# ECE_362_mini_project.net
KiCad netlist of a schematic drawn in EAGLE
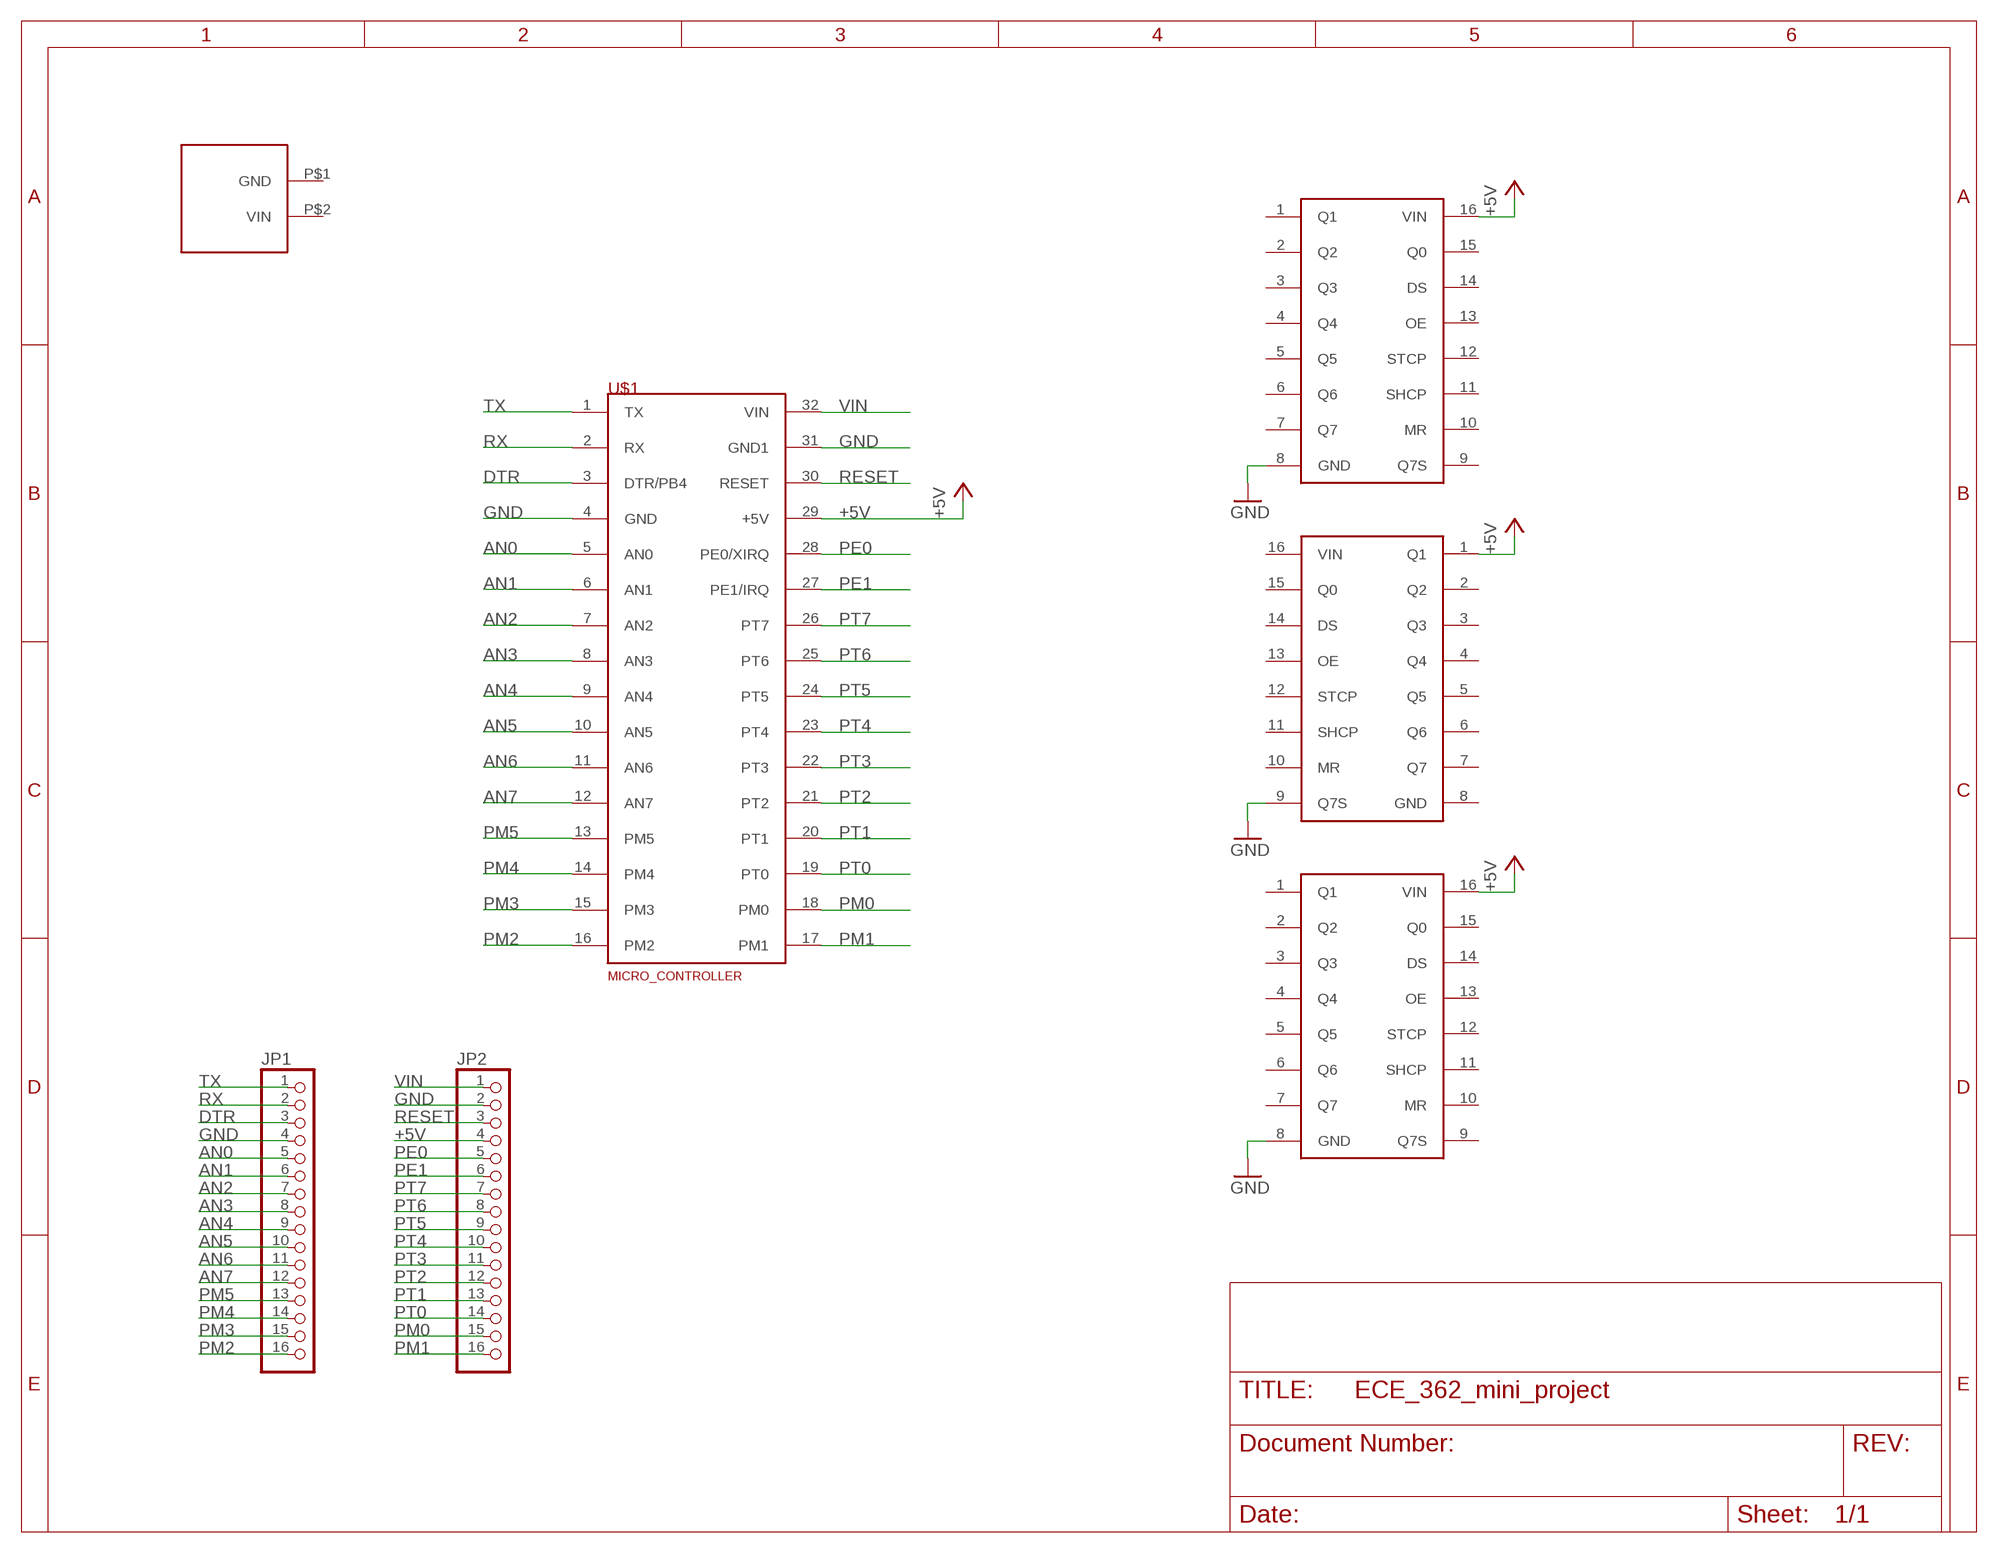
[diagram p0: schematic, sheet 1]

(export (version "E")
  (design (tool "Eeschema 10.0.6"))
  (components
    (comp (ref "JP1")
      (value "PINHD-1X16")
      (footprint "eagle-import:1X16")
      (libsource (lib "eagle-import") (part "PINHD-1X16"))
    )
    (comp (ref "JP2")
      (value "PINHD-1X16")
      (footprint "eagle-import:1X16")
      (libsource (lib "eagle-import") (part "PINHD-1X16"))
    )
    (comp (ref "U$1")
      (value "MICRO_CONTROLLER")
      (footprint "eagle-import:MICRO_CONTROLLER")
      (libsource (lib "eagle-import") (part "MICRO_CONTROLLER"))
    )
    (comp (ref "U$2")
      (value "SHIFT_REGISTER")
      (footprint "eagle-import:N5")
      (libsource (lib "eagle-import") (part "SHIFT_REGISTER"))
    )
    (comp (ref "U$3")
      (value "XT60")
      (footprint "eagle-import:XT60")
      (libsource (lib "eagle-import") (part "XT60"))
    )
    (comp (ref "U$4")
      (value "SHIFT_REGISTER")
      (footprint "eagle-import:N5")
      (libsource (lib "eagle-import") (part "SHIFT_REGISTER"))
    )
    (comp (ref "U$5")
      (value "SHIFT_REGISTER")
      (footprint "eagle-import:N5")
      (libsource (lib "eagle-import") (part "SHIFT_REGISTER"))
    )
  )
  (nets
    (net (code "1") (name "+5V") (class "Default")
      (node (ref "JP2") (pin "4") (pinfunction "4_4") (pintype "passive"))
      (node (ref "U$1") (pin "29") (pinfunction "+5V_29") (pintype "bidirectional"))
      (node (ref "U$2") (pin "16") (pinfunction "VIN_16") (pintype "bidirectional"))
      (node (ref "U$4") (pin "1") (pinfunction "Q1_1") (pintype "bidirectional"))
      (node (ref "U$5") (pin "16") (pinfunction "VIN_16") (pintype "bidirectional"))
    )
    (net (code "2") (name "/AN0") (class "Default")
      (node (ref "JP1") (pin "5") (pinfunction "5_5") (pintype "passive"))
      (node (ref "U$1") (pin "5") (pinfunction "AN0_5") (pintype "bidirectional"))
    )
    (net (code "3") (name "/AN1") (class "Default")
      (node (ref "JP1") (pin "6") (pinfunction "6_6") (pintype "passive"))
      (node (ref "U$1") (pin "6") (pinfunction "AN1_6") (pintype "bidirectional"))
    )
    (net (code "4") (name "/AN2") (class "Default")
      (node (ref "JP1") (pin "7") (pinfunction "7_7") (pintype "passive"))
      (node (ref "U$1") (pin "7") (pinfunction "AN2_7") (pintype "bidirectional"))
    )
    (net (code "5") (name "/AN3") (class "Default")
      (node (ref "JP1") (pin "8") (pinfunction "8_8") (pintype "passive"))
      (node (ref "U$1") (pin "8") (pinfunction "AN3_8") (pintype "bidirectional"))
    )
    (net (code "6") (name "/AN4") (class "Default")
      (node (ref "JP1") (pin "9") (pinfunction "9_9") (pintype "passive"))
      (node (ref "U$1") (pin "9") (pinfunction "AN4_9") (pintype "bidirectional"))
    )
    (net (code "7") (name "/AN5") (class "Default")
      (node (ref "JP1") (pin "10") (pinfunction "10_10") (pintype "passive"))
      (node (ref "U$1") (pin "10") (pinfunction "AN5_10") (pintype "bidirectional"))
    )
    (net (code "8") (name "/AN6") (class "Default")
      (node (ref "JP1") (pin "11") (pinfunction "11_11") (pintype "passive"))
      (node (ref "U$1") (pin "11") (pinfunction "AN6_11") (pintype "bidirectional"))
    )
    (net (code "9") (name "/AN7") (class "Default")
      (node (ref "JP1") (pin "12") (pinfunction "12_12") (pintype "passive"))
      (node (ref "U$1") (pin "12") (pinfunction "AN7_12") (pintype "bidirectional"))
    )
    (net (code "10") (name "/DTR") (class "Default")
      (node (ref "JP1") (pin "3") (pinfunction "3_3") (pintype "passive"))
      (node (ref "U$1") (pin "3") (pinfunction "DTR/PB4_3") (pintype "bidirectional"))
    )
    (net (code "11") (name "/PE0") (class "Default")
      (node (ref "JP2") (pin "5") (pinfunction "5_5") (pintype "passive"))
      (node (ref "U$1") (pin "28") (pinfunction "PE0/XIRQ_28") (pintype "bidirectional"))
    )
    (net (code "12") (name "/PE1") (class "Default")
      (node (ref "JP2") (pin "6") (pinfunction "6_6") (pintype "passive"))
      (node (ref "U$1") (pin "27") (pinfunction "PE1/IRQ_27") (pintype "bidirectional"))
    )
    (net (code "13") (name "/PM0") (class "Default")
      (node (ref "JP2") (pin "15") (pinfunction "15_15") (pintype "passive"))
      (node (ref "U$1") (pin "18") (pinfunction "PM0_18") (pintype "bidirectional"))
    )
    (net (code "14") (name "/PM1") (class "Default")
      (node (ref "JP2") (pin "16") (pinfunction "16_16") (pintype "passive"))
      (node (ref "U$1") (pin "17") (pinfunction "PM1_17") (pintype "bidirectional"))
    )
    (net (code "15") (name "/PM2") (class "Default")
      (node (ref "JP1") (pin "16") (pinfunction "16_16") (pintype "passive"))
      (node (ref "U$1") (pin "16") (pinfunction "PM2_16") (pintype "bidirectional"))
    )
    (net (code "16") (name "/PM3") (class "Default")
      (node (ref "JP1") (pin "15") (pinfunction "15_15") (pintype "passive"))
      (node (ref "U$1") (pin "15") (pinfunction "PM3_15") (pintype "bidirectional"))
    )
    (net (code "17") (name "/PM4") (class "Default")
      (node (ref "JP1") (pin "14") (pinfunction "14_14") (pintype "passive"))
      (node (ref "U$1") (pin "14") (pinfunction "PM4_14") (pintype "bidirectional"))
    )
    (net (code "18") (name "/PM5") (class "Default")
      (node (ref "JP1") (pin "13") (pinfunction "13_13") (pintype "passive"))
      (node (ref "U$1") (pin "13") (pinfunction "PM5_13") (pintype "bidirectional"))
    )
    (net (code "19") (name "/PT0") (class "Default")
      (node (ref "JP2") (pin "14") (pinfunction "14_14") (pintype "passive"))
      (node (ref "U$1") (pin "19") (pinfunction "PT0_19") (pintype "bidirectional"))
    )
    (net (code "20") (name "/PT1") (class "Default")
      (node (ref "JP2") (pin "13") (pinfunction "13_13") (pintype "passive"))
      (node (ref "U$1") (pin "20") (pinfunction "PT1_20") (pintype "bidirectional"))
    )
    (net (code "21") (name "/PT2") (class "Default")
      (node (ref "JP2") (pin "12") (pinfunction "12_12") (pintype "passive"))
      (node (ref "U$1") (pin "21") (pinfunction "PT2_21") (pintype "bidirectional"))
    )
    (net (code "22") (name "/PT3") (class "Default")
      (node (ref "JP2") (pin "11") (pinfunction "11_11") (pintype "passive"))
      (node (ref "U$1") (pin "22") (pinfunction "PT3_22") (pintype "bidirectional"))
    )
    (net (code "23") (name "/PT4") (class "Default")
      (node (ref "JP2") (pin "10") (pinfunction "10_10") (pintype "passive"))
      (node (ref "U$1") (pin "23") (pinfunction "PT4_23") (pintype "bidirectional"))
    )
    (net (code "24") (name "/PT5") (class "Default")
      (node (ref "JP2") (pin "9") (pinfunction "9_9") (pintype "passive"))
      (node (ref "U$1") (pin "24") (pinfunction "PT5_24") (pintype "bidirectional"))
    )
    (net (code "25") (name "/PT6") (class "Default")
      (node (ref "JP2") (pin "8") (pinfunction "8_8") (pintype "passive"))
      (node (ref "U$1") (pin "25") (pinfunction "PT6_25") (pintype "bidirectional"))
    )
    (net (code "26") (name "/PT7") (class "Default")
      (node (ref "JP2") (pin "7") (pinfunction "7_7") (pintype "passive"))
      (node (ref "U$1") (pin "26") (pinfunction "PT7_26") (pintype "bidirectional"))
    )
    (net (code "27") (name "/RESET") (class "Default")
      (node (ref "JP2") (pin "3") (pinfunction "3_3") (pintype "passive"))
      (node (ref "U$1") (pin "30") (pinfunction "RESET_30") (pintype "bidirectional"))
    )
    (net (code "28") (name "/RX") (class "Default")
      (node (ref "JP1") (pin "2") (pinfunction "2_2") (pintype "passive"))
      (node (ref "U$1") (pin "2") (pinfunction "RX_2") (pintype "bidirectional"))
    )
    (net (code "29") (name "/TX") (class "Default")
      (node (ref "JP1") (pin "1") (pinfunction "1_1") (pintype "passive"))
      (node (ref "U$1") (pin "1") (pinfunction "TX_1") (pintype "bidirectional"))
    )
    (net (code "30") (name "/VIN") (class "Default")
      (node (ref "JP2") (pin "1") (pinfunction "1_1") (pintype "passive"))
      (node (ref "U$1") (pin "32") (pinfunction "VIN_32") (pintype "bidirectional"))
    )
    (net (code "31") (name "GND") (class "Default")
      (node (ref "JP1") (pin "4") (pinfunction "4_4") (pintype "passive"))
      (node (ref "JP2") (pin "2") (pinfunction "2_2") (pintype "passive"))
      (node (ref "U$1") (pin "31") (pinfunction "GND1_31") (pintype "bidirectional"))
      (node (ref "U$1") (pin "4") (pinfunction "GND_4") (pintype "bidirectional"))
      (node (ref "U$2") (pin "8") (pinfunction "GND_8") (pintype "bidirectional"))
      (node (ref "U$4") (pin "9") (pinfunction "Q7S_9") (pintype "bidirectional"))
      (node (ref "U$5") (pin "8") (pinfunction "GND_8") (pintype "bidirectional"))
    )
    (net (code "32") (name "unconnected-(U$2-DS-Pad14)") (class "Default")
      (node (ref "U$2") (pin "14") (pinfunction "DS_14") (pintype "bidirectional"))
    )
    (net (code "33") (name "unconnected-(U$2-MR-Pad10)") (class "Default")
      (node (ref "U$2") (pin "10") (pinfunction "MR_10") (pintype "bidirectional"))
    )
    (net (code "34") (name "unconnected-(U$2-OE-Pad13)") (class "Default")
      (node (ref "U$2") (pin "13") (pinfunction "OE_13") (pintype "bidirectional"))
    )
    (net (code "35") (name "unconnected-(U$2-Q0-Pad15)") (class "Default")
      (node (ref "U$2") (pin "15") (pinfunction "Q0_15") (pintype "bidirectional"))
    )
    (net (code "36") (name "unconnected-(U$2-Q1-Pad1)") (class "Default")
      (node (ref "U$2") (pin "1") (pinfunction "Q1_1") (pintype "bidirectional"))
    )
    (net (code "37") (name "unconnected-(U$2-Q2-Pad2)") (class "Default")
      (node (ref "U$2") (pin "2") (pinfunction "Q2_2") (pintype "bidirectional"))
    )
    (net (code "38") (name "unconnected-(U$2-Q3-Pad3)") (class "Default")
      (node (ref "U$2") (pin "3") (pinfunction "Q3_3") (pintype "bidirectional"))
    )
    (net (code "39") (name "unconnected-(U$2-Q4-Pad4)") (class "Default")
      (node (ref "U$2") (pin "4") (pinfunction "Q4_4") (pintype "bidirectional"))
    )
    (net (code "40") (name "unconnected-(U$2-Q5-Pad5)") (class "Default")
      (node (ref "U$2") (pin "5") (pinfunction "Q5_5") (pintype "bidirectional"))
    )
    (net (code "41") (name "unconnected-(U$2-Q6-Pad6)") (class "Default")
      (node (ref "U$2") (pin "6") (pinfunction "Q6_6") (pintype "bidirectional"))
    )
    (net (code "42") (name "unconnected-(U$2-Q7-Pad7)") (class "Default")
      (node (ref "U$2") (pin "7") (pinfunction "Q7_7") (pintype "bidirectional"))
    )
    (net (code "43") (name "unconnected-(U$2-Q7S-Pad9)") (class "Default")
      (node (ref "U$2") (pin "9") (pinfunction "Q7S_9") (pintype "bidirectional"))
    )
    (net (code "44") (name "unconnected-(U$2-SHCP-Pad11)") (class "Default")
      (node (ref "U$2") (pin "11") (pinfunction "SHCP_11") (pintype "bidirectional"))
    )
    (net (code "45") (name "unconnected-(U$2-STCP-Pad12)") (class "Default")
      (node (ref "U$2") (pin "12") (pinfunction "STCP_12") (pintype "bidirectional"))
    )
    (net (code "46") (name "unconnected-(U$3-GND-PadP$1)") (class "Default")
      (node (ref "U$3") (pin "P$1") (pinfunction "GND_P$1") (pintype "bidirectional"))
    )
    (net (code "47") (name "unconnected-(U$3-VIN-PadP$2)") (class "Default")
      (node (ref "U$3") (pin "P$2") (pinfunction "VIN_P$2") (pintype "bidirectional"))
    )
    (net (code "48") (name "unconnected-(U$4-DS-Pad14)") (class "Default")
      (node (ref "U$4") (pin "14") (pinfunction "DS_14") (pintype "bidirectional"))
    )
    (net (code "49") (name "unconnected-(U$4-GND-Pad8)") (class "Default")
      (node (ref "U$4") (pin "8") (pinfunction "GND_8") (pintype "bidirectional"))
    )
    (net (code "50") (name "unconnected-(U$4-MR-Pad10)") (class "Default")
      (node (ref "U$4") (pin "10") (pinfunction "MR_10") (pintype "bidirectional"))
    )
    (net (code "51") (name "unconnected-(U$4-OE-Pad13)") (class "Default")
      (node (ref "U$4") (pin "13") (pinfunction "OE_13") (pintype "bidirectional"))
    )
    (net (code "52") (name "unconnected-(U$4-Q0-Pad15)") (class "Default")
      (node (ref "U$4") (pin "15") (pinfunction "Q0_15") (pintype "bidirectional"))
    )
    (net (code "53") (name "unconnected-(U$4-Q2-Pad2)") (class "Default")
      (node (ref "U$4") (pin "2") (pinfunction "Q2_2") (pintype "bidirectional"))
    )
    (net (code "54") (name "unconnected-(U$4-Q3-Pad3)") (class "Default")
      (node (ref "U$4") (pin "3") (pinfunction "Q3_3") (pintype "bidirectional"))
    )
    (net (code "55") (name "unconnected-(U$4-Q4-Pad4)") (class "Default")
      (node (ref "U$4") (pin "4") (pinfunction "Q4_4") (pintype "bidirectional"))
    )
    (net (code "56") (name "unconnected-(U$4-Q5-Pad5)") (class "Default")
      (node (ref "U$4") (pin "5") (pinfunction "Q5_5") (pintype "bidirectional"))
    )
    (net (code "57") (name "unconnected-(U$4-Q6-Pad6)") (class "Default")
      (node (ref "U$4") (pin "6") (pinfunction "Q6_6") (pintype "bidirectional"))
    )
    (net (code "58") (name "unconnected-(U$4-Q7-Pad7)") (class "Default")
      (node (ref "U$4") (pin "7") (pinfunction "Q7_7") (pintype "bidirectional"))
    )
    (net (code "59") (name "unconnected-(U$4-SHCP-Pad11)") (class "Default")
      (node (ref "U$4") (pin "11") (pinfunction "SHCP_11") (pintype "bidirectional"))
    )
    (net (code "60") (name "unconnected-(U$4-STCP-Pad12)") (class "Default")
      (node (ref "U$4") (pin "12") (pinfunction "STCP_12") (pintype "bidirectional"))
    )
    (net (code "61") (name "unconnected-(U$4-VIN-Pad16)") (class "Default")
      (node (ref "U$4") (pin "16") (pinfunction "VIN_16") (pintype "bidirectional"))
    )
    (net (code "62") (name "unconnected-(U$5-DS-Pad14)") (class "Default")
      (node (ref "U$5") (pin "14") (pinfunction "DS_14") (pintype "bidirectional"))
    )
    (net (code "63") (name "unconnected-(U$5-MR-Pad10)") (class "Default")
      (node (ref "U$5") (pin "10") (pinfunction "MR_10") (pintype "bidirectional"))
    )
    (net (code "64") (name "unconnected-(U$5-OE-Pad13)") (class "Default")
      (node (ref "U$5") (pin "13") (pinfunction "OE_13") (pintype "bidirectional"))
    )
    (net (code "65") (name "unconnected-(U$5-Q0-Pad15)") (class "Default")
      (node (ref "U$5") (pin "15") (pinfunction "Q0_15") (pintype "bidirectional"))
    )
    (net (code "66") (name "unconnected-(U$5-Q1-Pad1)") (class "Default")
      (node (ref "U$5") (pin "1") (pinfunction "Q1_1") (pintype "bidirectional"))
    )
    (net (code "67") (name "unconnected-(U$5-Q2-Pad2)") (class "Default")
      (node (ref "U$5") (pin "2") (pinfunction "Q2_2") (pintype "bidirectional"))
    )
    (net (code "68") (name "unconnected-(U$5-Q3-Pad3)") (class "Default")
      (node (ref "U$5") (pin "3") (pinfunction "Q3_3") (pintype "bidirectional"))
    )
    (net (code "69") (name "unconnected-(U$5-Q4-Pad4)") (class "Default")
      (node (ref "U$5") (pin "4") (pinfunction "Q4_4") (pintype "bidirectional"))
    )
    (net (code "70") (name "unconnected-(U$5-Q5-Pad5)") (class "Default")
      (node (ref "U$5") (pin "5") (pinfunction "Q5_5") (pintype "bidirectional"))
    )
    (net (code "71") (name "unconnected-(U$5-Q6-Pad6)") (class "Default")
      (node (ref "U$5") (pin "6") (pinfunction "Q6_6") (pintype "bidirectional"))
    )
    (net (code "72") (name "unconnected-(U$5-Q7-Pad7)") (class "Default")
      (node (ref "U$5") (pin "7") (pinfunction "Q7_7") (pintype "bidirectional"))
    )
    (net (code "73") (name "unconnected-(U$5-Q7S-Pad9)") (class "Default")
      (node (ref "U$5") (pin "9") (pinfunction "Q7S_9") (pintype "bidirectional"))
    )
    (net (code "74") (name "unconnected-(U$5-SHCP-Pad11)") (class "Default")
      (node (ref "U$5") (pin "11") (pinfunction "SHCP_11") (pintype "bidirectional"))
    )
    (net (code "75") (name "unconnected-(U$5-STCP-Pad12)") (class "Default")
      (node (ref "U$5") (pin "12") (pinfunction "STCP_12") (pintype "bidirectional"))
    )
  )
)
